# Power.net
KiCad netlist of a schematic drawn in Altium Designer
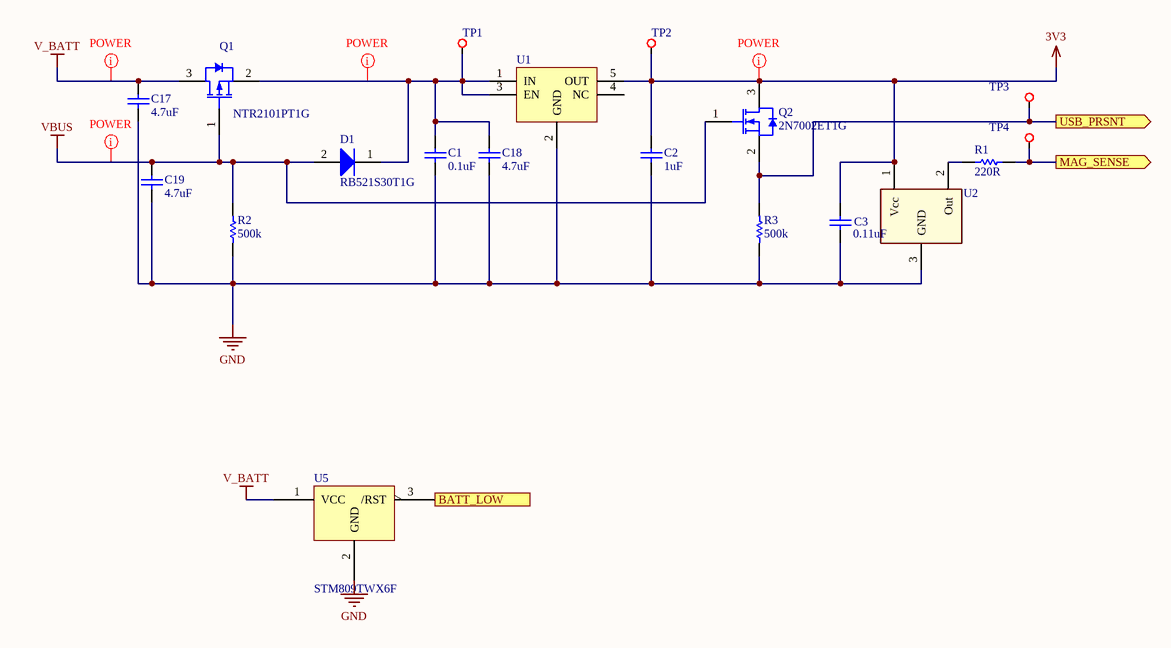
[diagram p0: Power.SchDoc]

(export (version "E")
  (design (tool "Eeschema 10.0.6"))
  (components
    (comp (ref "C1")
      (value "0.1uF")
      (footprint "0402cap")
      (description "0402 Ceramic Chip Capacitor - Standard")
      (fields (field (name "Comment") "C0402"))
      (libsource (lib "Chip Capacitor") (part "C0402"))
    )
    (comp (ref "C2")
      (value "1uF")
      (footprint "0402cap")
      (description "0402 Ceramic Chip Capacitor - Standard")
      (fields (field (name "Comment") "C0402"))
      (libsource (lib "Chip Capacitor") (part "C0402"))
    )
    (comp (ref "C3")
      (value "0.11uF")
      (footprint "0402cap")
      (description "0402 Ceramic Chip Capacitor - Standard")
      (fields (field (name "Comment") "C0402"))
      (libsource (lib "Chip Capacitor") (part "C0402"))
    )
    (comp (ref "C17")
      (value "4.7uF")
      (footprint "0603CAP")
      (description "0603 Ceramic Chip Capacitor - Standard")
      (fields (field (name "Comment") "C0603"))
      (libsource (lib "lib-Standard") (part "C0603"))
    )
    (comp (ref "C18")
      (value "4.7uF")
      (footprint "0603CAP")
      (description "0603 Ceramic Chip Capacitor - Standard")
      (fields (field (name "Comment") "C0603"))
      (libsource (lib "lib-Standard") (part "C0603"))
    )
    (comp (ref "C19")
      (value "4.7uF")
      (footprint "0603CAP")
      (description "0603 Ceramic Chip Capacitor - Standard")
      (fields (field (name "Comment") "C0603"))
      (libsource (lib "lib-Standard") (part "C0603"))
    )
    (comp (ref "D1")
      (value "RB521S30T1G")
      (footprint "ONSC-SOD-523-2-502-01_V")
      (description "Schottky Barrier Diode, 2-Pin SOD-523, Pb-Free, Tape and Reel")
      (fields (field (name "MANUFACTURER") "On Semiconductor"))
      (libsource (lib "Altium Content Vault") (part "ONSC-D-K1A2-2"))
    )
    (comp (ref "Q1")
      (value "NTR2101PT1G")
      (footprint "ONSC-SOT-23-3-318-08_V")
      (description "Small Signal MOSFET, -8 V, -3.7 A, Single P-Channel, 3-Pin SOT-23, Pb-Free, Tape and Reel")
      (fields (field (name "MANUFACTURER") "On Semiconductor"))
      (libsource (lib "ON Semi MOSFETs") (part "NTR2101PT1G"))
    )
    (comp (ref "Q2")
      (value "2N7002ET1G")
      (footprint "ONSC-SOT-23-3-318-08_V")
      (description "Small Signal MOSFET, 60 V, 310 mA, Single, N-Channel, 3-Pin SOT-23, Pb-Free, Tape and Reel")
      (fields (field (name "MANUFACTURER") "On Semiconductor"))
      (libsource (lib "ON Semi MOSFETs") (part "2N7002ET1G"))
    )
    (comp (ref "R1")
      (value "220R")
      (footprint "0402RES")
      (description "0402 Chip Resistor - Standard")
      (fields (field (name "Comment") "R0402"))
      (libsource (lib "Chip Resistor") (part "R0402"))
    )
    (comp (ref "R2")
      (value "500k")
      (footprint "0402RES")
      (description "0402 Chip Resistor - Standard")
      (fields (field (name "Comment") "R0402"))
      (libsource (lib "Chip Resistor") (part "R0402"))
    )
    (comp (ref "R3")
      (value "500k")
      (footprint "0402RES")
      (description "0402 Chip Resistor - Standard")
      (fields (field (name "Comment") "R0402"))
      (libsource (lib "Chip Resistor") (part "R0402"))
    )
    (comp (ref "TP1")
      (value "TESTPOINT")
      (footprint "TP R25")
      (description "0.025\" Round Test Point")
      (fields (field (name "PART NUMBER") "1613"))
      (libsource (lib "TestPoints") (part "TP25"))
    )
    (comp (ref "TP2")
      (value "TESTPOINT")
      (footprint "TP R25")
      (description "0.025\" Round Test Point")
      (fields (field (name "PART NUMBER") "1613"))
      (libsource (lib "TestPoints") (part "TP25"))
    )
    (comp (ref "TP3")
      (value "TESTPOINT")
      (footprint "TP R25")
      (description "0.025\" Round Test Point")
      (fields (field (name "PART NUMBER") "1613"))
      (libsource (lib "TestPoints") (part "TP25"))
    )
    (comp (ref "TP4")
      (value "TESTPOINT")
      (footprint "TP R25")
      (description "0.025\" Round Test Point")
      (fields (field (name "PART NUMBER") "1613"))
      (libsource (lib "TestPoints") (part "TP25"))
    )
    (comp (ref "U1")
      (value "IC REG LINEAR 3.3V 200MA ESV")
      (footprint "TCR2EE33,LM(CT")
      (description "Linear Voltage Regulator IC Positive Fixed 1 Output  200mA ESV")
      (libsource (lib "lib-VoltageRegulators") (part "TCR2EE33,LM(CT"))
    )
    (comp (ref "U2")
      (value "DRV5032FBDBZT")
      (footprint "SOT-23")
      (description "Hall Effect Sensor")
      (libsource (lib "VHF Library") (part "DRV5032FBDBZT"))
    )
    (comp (ref "U5")
      (value "STM809TWX6F")
      (footprint "SOT103P237X112-3N")
      (description "IC MPU RESET CIRC 3.08V SOT23")
      (libsource (lib "lib-IC_Other") (part "STM809TWX6F"))
    )
  )
  (nets
    (net (code "1") (name "/BATT_LOW") (class "Default")
      (node (ref "U5") (pin "3") (pinfunction "/RST_3") (pintype "passive"))
    )
    (net (code "2") (name "/MAG_SENSE") (class "Default")
      (node (ref "R1") (pin "2") (pinfunction "2_2") (pintype "passive"))
      (node (ref "TP4") (pin "1") (pinfunction "1_1") (pintype "passive"))
    )
    (net (code "3") (name "/USB_PRSNT") (class "Default")
      (node (ref "Q2") (pin "2") (pinfunction "S_2") (pintype "passive"))
      (node (ref "R3") (pin "2") (pinfunction "2_2") (pintype "passive"))
      (node (ref "TP3") (pin "1") (pinfunction "1_1") (pintype "passive"))
    )
    (net (code "4") (name "3V3") (class "Default")
      (node (ref "C2") (pin "2") (pinfunction "2_2") (pintype "passive"))
      (node (ref "C3") (pin "2") (pinfunction "2_2") (pintype "passive"))
      (node (ref "Q2") (pin "3") (pinfunction "D_3") (pintype "passive"))
      (node (ref "TP2") (pin "1") (pinfunction "1_1") (pintype "passive"))
      (node (ref "U1") (pin "5") (pinfunction "OUT_5") (pintype "passive"))
      (node (ref "U2") (pin "1") (pinfunction "Vcc_1") (pintype "passive"))
    )
    (net (code "5") (name "GND") (class "Default")
      (node (ref "C1") (pin "1") (pinfunction "1_1") (pintype "passive"))
      (node (ref "C17") (pin "1") (pinfunction "1_1") (pintype "passive"))
      (node (ref "C18") (pin "1") (pinfunction "1_1") (pintype "passive"))
      (node (ref "C19") (pin "1") (pinfunction "1_1") (pintype "passive"))
      (node (ref "C2") (pin "1") (pinfunction "1_1") (pintype "passive"))
      (node (ref "C3") (pin "1") (pinfunction "1_1") (pintype "passive"))
      (node (ref "R2") (pin "1") (pinfunction "1_1") (pintype "passive"))
      (node (ref "R3") (pin "1") (pinfunction "1_1") (pintype "passive"))
      (node (ref "U1") (pin "2") (pinfunction "GND_2") (pintype "passive"))
      (node (ref "U2") (pin "3") (pinfunction "GND_3") (pintype "passive"))
      (node (ref "U5") (pin "2") (pinfunction "GND_2") (pintype "passive"))
    )
    (net (code "6") (name "Net-(D1-K)") (class "Default")
      (node (ref "C1") (pin "2") (pinfunction "2_2") (pintype "passive"))
      (node (ref "C18") (pin "2") (pinfunction "2_2") (pintype "passive"))
      (node (ref "D1") (pin "1") (pinfunction "K_1") (pintype "passive"))
      (node (ref "Q1") (pin "2") (pinfunction "S_2") (pintype "passive"))
      (node (ref "TP1") (pin "1") (pinfunction "1_1") (pintype "passive"))
      (node (ref "U1") (pin "1") (pinfunction "IN_1") (pintype "passive"))
      (node (ref "U1") (pin "3") (pinfunction "EN_3") (pintype "passive"))
    )
    (net (code "7") (name "Net-(U2-Out)") (class "Default")
      (node (ref "R1") (pin "1") (pinfunction "1_1") (pintype "passive"))
      (node (ref "U2") (pin "2") (pinfunction "Out_2") (pintype "passive"))
    )
    (net (code "8") (name "VBUS") (class "Default")
      (node (ref "C19") (pin "2") (pinfunction "2_2") (pintype "passive"))
      (node (ref "D1") (pin "2") (pinfunction "A_2") (pintype "passive"))
      (node (ref "Q1") (pin "1") (pinfunction "G_1") (pintype "passive"))
      (node (ref "Q2") (pin "1") (pinfunction "G_1") (pintype "passive"))
      (node (ref "R2") (pin "2") (pinfunction "2_2") (pintype "passive"))
    )
    (net (code "9") (name "V_BATT") (class "Default")
      (node (ref "C17") (pin "2") (pinfunction "2_2") (pintype "passive"))
      (node (ref "Q1") (pin "3") (pinfunction "D_3") (pintype "passive"))
      (node (ref "U5") (pin "1") (pinfunction "VCC_1") (pintype "passive"))
    )
    (net (code "10") (name "unconnected-(U1-NC-Pad4)") (class "Default")
      (node (ref "U1") (pin "4") (pinfunction "NC_4") (pintype "passive"))
    )
  )
)
